# Clamp.net
KiCad netlist of a schematic drawn in Altium Designer
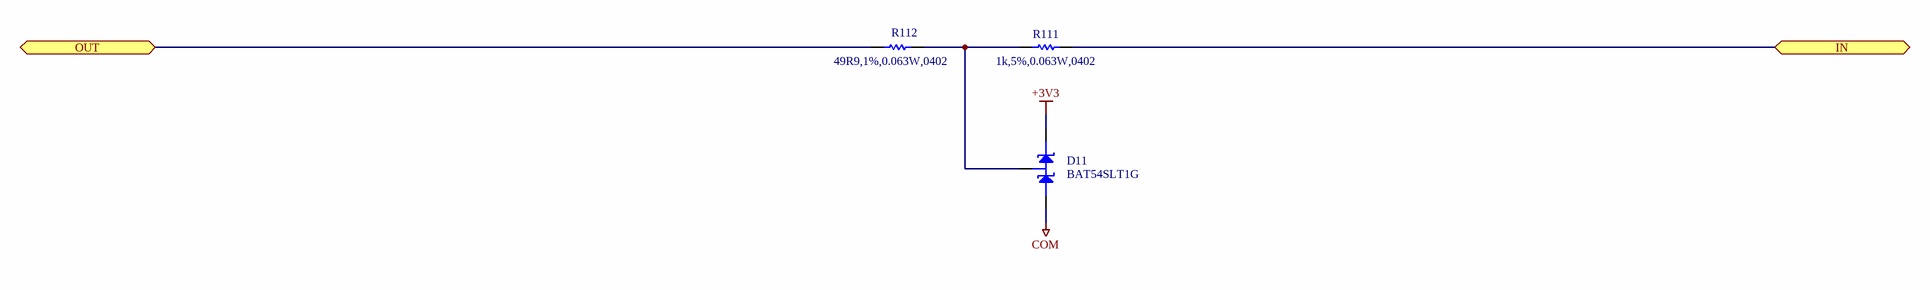
[diagram p0: Clamp.SchDoc]

(export (version "E")
  (design (tool "Eeschema 10.0.6"))
  (components
    (comp (ref "D11")
      (value "BAT54SLT1G")
      (footprint "SOT95P240X120-3N")
      (description "Diode Array 1 Pair Series Connection 30 V 200mA (DC) Surface Mount TO-236-3, SC-59, SOT-23-3")
      (fields
        (field (name "VENDOR 1 PART NUMBER") "BAT54SLT1GOSCT-ND")
        (field (name "CREATEDBY") "Judd Foster")
      )
      (libsource (lib "Component Library") (part "DIODE,Array,Schottky,Series,30V,200mA,SOT23"))
    )
    (comp (ref "R111")
      (value "1k,5%,0.063W,0402")
      (footprint "RESC1005X04N")
      (description "1 kOhms ï¿½5% 0.063W, 1/16W Chip Resistor 0402 (1005 Metric) Automotive AEC-Q200 Thick Film")
      (fields
        (field (name "MANUFACTURER 1 PART NUMBER") "RMCF0402JT1K00")
        (field (name "VENDOR 1 PART NUMBER") "RMCF0402JT1K00CT-ND")
        (field (name "CREATEDBY") "Judd Foster")
      )
      (libsource (lib "Component Library") (part "RES,1k,5%,0.063W,0402"))
    )
    (comp (ref "R112")
      (value "49R9,1%,0.063W,0402")
      (footprint "RESC1005X04N")
      (description "49.9 Ohms Â±1% 0.063W, 1/16W Chip Resistor 0402 (1005 Metric) Moisture Resistant Thick Film")
      (fields
        (field (name "MANUFACTURER 1 PART NUMBER") "RC0402FR-0749R9L")
        (field (name "VENDOR 1 PART NUMBER") "311-49.9LRCT-ND")
        (field (name "CREATEDBY") "Judd Foster")
      )
      (libsource (lib "Component Library") (part "RES,49R9,1%,0.063W,0402"))
    )
  )
  (nets
    (net (code "1") (name "+3V3") (class "Default")
      (node (ref "D11") (pin "2") (pinfunction "C_2") (pintype "passive"))
    )
    (net (code "2") (name "/IN") (class "Default")
      (node (ref "R111") (pin "2") (pinfunction "2_2") (pintype "passive"))
    )
    (net (code "3") (name "/OUT") (class "Default")
      (node (ref "R112") (pin "1") (pinfunction "1_1") (pintype "passive"))
    )
    (net (code "4") (name "COM") (class "Default")
      (node (ref "D11") (pin "1") (pinfunction "A_1") (pintype "passive"))
    )
    (net (code "5") (name "Net-(D11-C{slash}A)") (class "Default")
      (node (ref "D11") (pin "3") (pinfunction "C/A_3") (pintype "passive"))
      (node (ref "R111") (pin "1") (pinfunction "1_1") (pintype "passive"))
      (node (ref "R112") (pin "2") (pinfunction "2_2") (pintype "passive"))
    )
  )
)
